# 08_-_PERIPHERALS_C.net
KiCad netlist of a schematic drawn in Altium Designer
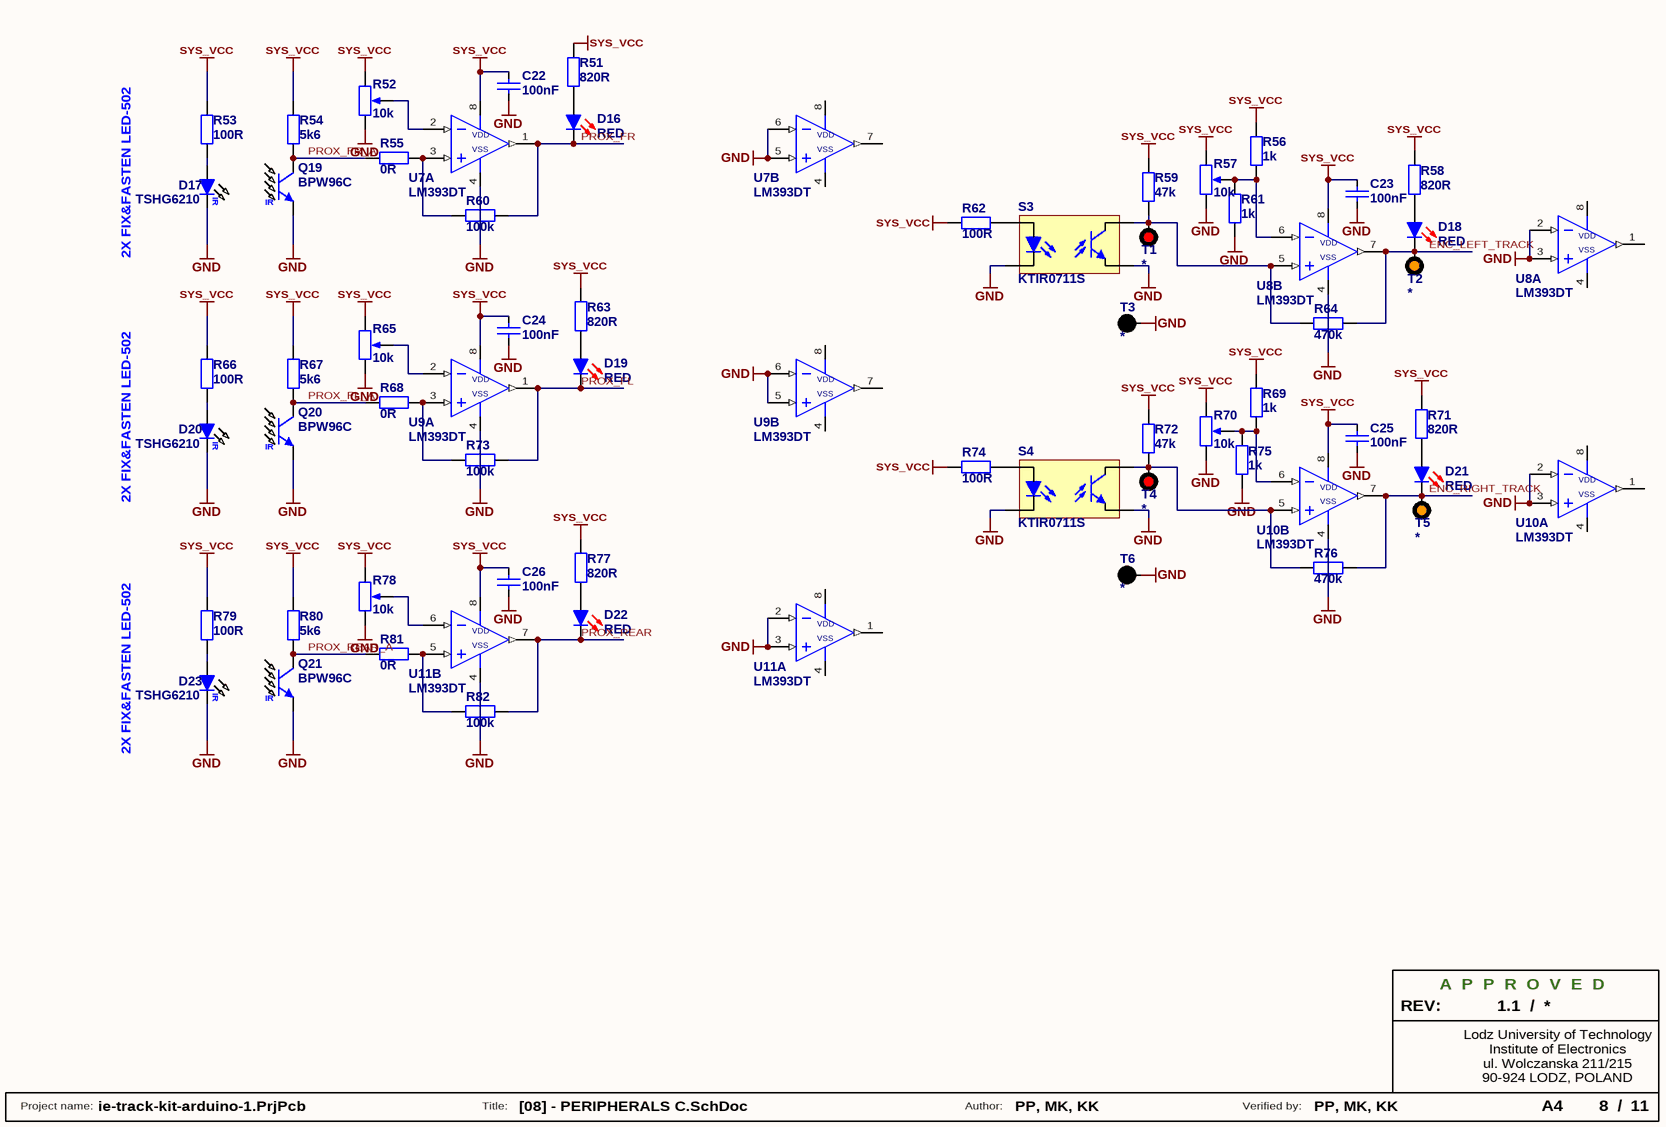
[diagram p0: [08] - PERIPHERALS C.SchDoc]

(export (version "E")
  (design (tool "Eeschema 10.0.6"))
  (components
    (comp (ref "C22")
      (value "100nF")
      (footprint "C0805")
      (description "Capacitor")
      (libsource (lib "capacitors") (part "Cap"))
    )
    (comp (ref "C23")
      (value "100nF")
      (footprint "C0805")
      (description "Capacitor")
      (libsource (lib "capacitors") (part "Cap"))
    )
    (comp (ref "C24")
      (value "100nF")
      (footprint "C0805")
      (description "Capacitor")
      (libsource (lib "capacitors") (part "Cap"))
    )
    (comp (ref "C25")
      (value "100nF")
      (footprint "C0805")
      (description "Capacitor")
      (libsource (lib "capacitors") (part "Cap"))
    )
    (comp (ref "C26")
      (value "100nF")
      (footprint "C0805")
      (description "Capacitor")
      (libsource (lib "capacitors") (part "Cap"))
    )
    (comp (ref "D16")
      (value "RED")
      (footprint "LED0805R")
      (description "RED LED")
      (libsource (lib "leds") (part "LED_RED"))
    )
    (comp (ref "D17")
      (value "TSHG6210")
      (footprint "LED-502")
      (description "IR transmitter; 5mm; 850nm; transparent; 230mW; 10°; THT; 1.5÷1.8V")
      (libsource (lib "leds") (part "TSHG6210"))
    )
    (comp (ref "D18")
      (value "RED")
      (footprint "LED0805R")
      (description "RED LED")
      (libsource (lib "leds") (part "LED_RED"))
    )
    (comp (ref "D19")
      (value "RED")
      (footprint "LED0805R")
      (description "RED LED")
      (libsource (lib "leds") (part "LED_RED"))
    )
    (comp (ref "D20")
      (value "TSHG6210")
      (footprint "LED-502")
      (description "IR transmitter; 5mm; 850nm; transparent; 230mW; 10°; THT; 1.5÷1.8V")
      (libsource (lib "leds") (part "TSHG6210"))
    )
    (comp (ref "D21")
      (value "RED")
      (footprint "LED0805R")
      (description "RED LED")
      (libsource (lib "leds") (part "LED_RED"))
    )
    (comp (ref "D22")
      (value "RED")
      (footprint "LED0805R")
      (description "RED LED")
      (libsource (lib "leds") (part "LED_RED"))
    )
    (comp (ref "D23")
      (value "TSHG6210")
      (footprint "LED-502")
      (description "IR transmitter; 5mm; 850nm; transparent; 230mW; 10°; THT; 1.5÷1.8V")
      (libsource (lib "leds") (part "TSHG6210"))
    )
    (comp (ref "Q19")
      (value "BPW96C")
      (footprint "LED-502")
      (description "Phototransistor; λp max:850nm; 70V; 20°; Lens: transparent; Ø:5mm")
      (libsource (lib "photoelements") (part "BPW96C"))
    )
    (comp (ref "Q20")
      (value "BPW96C")
      (footprint "LED-502")
      (description "Phototransistor; λp max:850nm; 70V; 20°; Lens: transparent; Ø:5mm")
      (libsource (lib "photoelements") (part "BPW96C"))
    )
    (comp (ref "Q21")
      (value "BPW96C")
      (footprint "LED-502")
      (description "Phototransistor; λp max:850nm; 70V; 20°; Lens: transparent; Ø:5mm")
      (libsource (lib "photoelements") (part "BPW96C"))
    )
    (comp (ref "R51")
      (value "820R")
      (footprint "R0805")
      (description "Resistor")
      (libsource (lib "") (part "Res_1"))
    )
    (comp (ref "R52")
      (value "10k")
      (footprint "3305SMD")
      (description "3305SMD-10K")
      (libsource (lib "resistors") (part "3305SMD-10K"))
    )
    (comp (ref "R53")
      (value "100R")
      (footprint "R0805")
      (description "Resistor")
      (libsource (lib "") (part "Res_1"))
    )
    (comp (ref "R54")
      (value "5k6")
      (footprint "R0805")
      (description "Resistor")
      (libsource (lib "") (part "Res_1"))
    )
    (comp (ref "R55")
      (value "0R")
      (footprint "R0805")
      (description "Resistor")
      (libsource (lib "resistors") (part "Res"))
    )
    (comp (ref "R56")
      (value "1k")
      (footprint "R0805")
      (description "Resistor")
      (libsource (lib "") (part "Res_1"))
    )
    (comp (ref "R57")
      (value "10k")
      (footprint "3305SMD")
      (description "3305SMD-10K")
      (libsource (lib "resistors") (part "3305SMD-10K"))
    )
    (comp (ref "R58")
      (value "820R")
      (footprint "R0805")
      (description "Resistor")
      (libsource (lib "") (part "Res_1"))
    )
    (comp (ref "R59")
      (value "47k")
      (footprint "R0805")
      (description "Resistor")
      (libsource (lib "") (part "Res_3"))
    )
    (comp (ref "R60")
      (value "100k")
      (footprint "R0805")
      (description "Resistor")
      (libsource (lib "resistors") (part "Res"))
    )
    (comp (ref "R61")
      (value "1k")
      (footprint "R0805")
      (description "Resistor")
      (libsource (lib "") (part "Res_1"))
    )
    (comp (ref "R62")
      (value "100R")
      (footprint "R0805")
      (description "Resistor")
      (libsource (lib "") (part "Res_2"))
    )
    (comp (ref "R63")
      (value "820R")
      (footprint "R0805")
      (description "Resistor")
      (libsource (lib "") (part "Res_1"))
    )
    (comp (ref "R64")
      (value "470k")
      (footprint "R0805")
      (description "Resistor")
      (libsource (lib "resistors") (part "Res"))
    )
    (comp (ref "R65")
      (value "10k")
      (footprint "3305SMD")
      (description "3305SMD-10K")
      (libsource (lib "resistors") (part "3305SMD-10K"))
    )
    (comp (ref "R66")
      (value "100R")
      (footprint "R0805")
      (description "Resistor")
      (libsource (lib "") (part "Res_1"))
    )
    (comp (ref "R67")
      (value "5k6")
      (footprint "R0805")
      (description "Resistor")
      (libsource (lib "") (part "Res_1"))
    )
    (comp (ref "R68")
      (value "0R")
      (footprint "R0805")
      (description "Resistor")
      (libsource (lib "resistors") (part "Res"))
    )
    (comp (ref "R69")
      (value "1k")
      (footprint "R0805")
      (description "Resistor")
      (libsource (lib "") (part "Res_1"))
    )
    (comp (ref "R70")
      (value "10k")
      (footprint "3305SMD")
      (description "3305SMD-10K")
      (libsource (lib "resistors") (part "3305SMD-10K"))
    )
    (comp (ref "R71")
      (value "820R")
      (footprint "R0805")
      (description "Resistor")
      (libsource (lib "") (part "Res_1"))
    )
    (comp (ref "R72")
      (value "47k")
      (footprint "R0805")
      (description "Resistor")
      (libsource (lib "") (part "Res_3"))
    )
    (comp (ref "R73")
      (value "100k")
      (footprint "R0805")
      (description "Resistor")
      (libsource (lib "resistors") (part "Res"))
    )
    (comp (ref "R74")
      (value "100R")
      (footprint "R0805")
      (description "Resistor")
      (libsource (lib "") (part "Res_2"))
    )
    (comp (ref "R75")
      (value "1k")
      (footprint "R0805")
      (description "Resistor")
      (libsource (lib "") (part "Res_1"))
    )
    (comp (ref "R76")
      (value "470k")
      (footprint "R0805")
      (description "Resistor")
      (libsource (lib "resistors") (part "Res"))
    )
    (comp (ref "R77")
      (value "820R")
      (footprint "R0805")
      (description "Resistor")
      (libsource (lib "") (part "Res_1"))
    )
    (comp (ref "R78")
      (value "10k")
      (footprint "3305SMD")
      (description "3305SMD-10K")
      (libsource (lib "resistors") (part "3305SMD-10K"))
    )
    (comp (ref "R79")
      (value "100R")
      (footprint "R0805")
      (description "Resistor")
      (libsource (lib "") (part "Res_1"))
    )
    (comp (ref "R80")
      (value "5k6")
      (footprint "R0805")
      (description "Resistor")
      (libsource (lib "") (part "Res_1"))
    )
    (comp (ref "R81")
      (value "0R")
      (footprint "R0805")
      (description "Resistor")
      (libsource (lib "resistors") (part "Res"))
    )
    (comp (ref "R82")
      (value "100k")
      (footprint "R0805")
      (description "Resistor")
      (libsource (lib "resistors") (part "Res"))
    )
    (comp (ref "S3")
      (value "KTIR0711S")
      (footprint "KTIR0711S_wide_pads")
      (description "SUBMINIATURE, HIGH SENSITIVITY PHOTOINTERRUPTER")
      (libsource (lib "photoelectric_sensors") (part "KTIR0711S"))
    )
    (comp (ref "S4")
      (value "KTIR0711S")
      (footprint "KTIR0711S_wide_pads")
      (description "SUBMINIATURE, HIGH SENSITIVITY PHOTOINTERRUPTER")
      (libsource (lib "photoelectric_sensors") (part "KTIR0711S"))
    )
    (comp (ref "T1")
      (value "*")
      (footprint "Keystone_5000_RED")
      (description "Keystone 5000 Test Point (RED)")
      (libsource (lib "test_points") (part "Keystone 5000 Test Point"))
    )
    (comp (ref "T2")
      (value "*")
      (footprint "Keystone_5003_ORANGE")
      (description "Keystone 5003 Test Point (ORANGE)")
      (libsource (lib "test_points") (part "Keystone 5003 Test Point"))
    )
    (comp (ref "T3")
      (value "*")
      (footprint "Keystone_5001_BLACK")
      (description "Keystone 5001 Test Point (BLACK)")
      (libsource (lib "test_points") (part "Keystone 5001 Test Point"))
    )
    (comp (ref "T4")
      (value "*")
      (footprint "Keystone_5000_RED")
      (description "Keystone 5000 Test Point (RED)")
      (libsource (lib "test_points") (part "Keystone 5000 Test Point"))
    )
    (comp (ref "T5")
      (value "*")
      (footprint "Keystone_5003_ORANGE")
      (description "Keystone 5003 Test Point (ORANGE)")
      (libsource (lib "test_points") (part "Keystone 5003 Test Point"))
    )
    (comp (ref "T6")
      (value "*")
      (footprint "Keystone_5001_BLACK")
      (description "Keystone 5001 Test Point (BLACK)")
      (libsource (lib "test_points") (part "Keystone 5001 Test Point"))
    )
    (comp (ref "U7")
      (value "LM393DT")
      (footprint "SO8")
      (description "Low power dual voltage comparators")
      (libsource (lib "comparators") (part "LM393DT"))
    )
    (comp (ref "U8")
      (value "LM393DT")
      (footprint "SO8")
      (description "Low power dual voltage comparators")
      (libsource (lib "comparators") (part "LM393DT"))
    )
    (comp (ref "U9")
      (value "LM393DT")
      (footprint "SO8")
      (description "Low power dual voltage comparators")
      (libsource (lib "comparators") (part "LM393DT"))
    )
    (comp (ref "U10")
      (value "LM393DT")
      (footprint "SO8")
      (description "Low power dual voltage comparators")
      (libsource (lib "comparators") (part "LM393DT"))
    )
    (comp (ref "U11")
      (value "LM393DT")
      (footprint "SO8")
      (description "Low power dual voltage comparators")
      (libsource (lib "comparators") (part "LM393DT"))
    )
  )
  (nets
    (net (code "1") (name "/ENC_LEFT_TRACK") (class "Default")
      (node (ref "D18") (pin "2") (pinfunction "K_2") (pintype "passive"))
      (node (ref "R64") (pin "2") (pinfunction "2_2") (pintype "passive"))
      (node (ref "T2") (pin "0") (pinfunction "0_0") (pintype "passive"))
      (node (ref "U8") (pin "7") (pinfunction "OUT_7") (pintype "output"))
    )
    (net (code "2") (name "/ENC_RIGHT_TRACK") (class "Default")
      (node (ref "D21") (pin "2") (pinfunction "K_2") (pintype "passive"))
      (node (ref "R76") (pin "2") (pinfunction "2_2") (pintype "passive"))
      (node (ref "T5") (pin "0") (pinfunction "0_0") (pintype "passive"))
      (node (ref "U10") (pin "7") (pinfunction "OUT_7") (pintype "output"))
    )
    (net (code "3") (name "/PROX_FL") (class "Default")
      (node (ref "D19") (pin "2") (pinfunction "K_2") (pintype "passive"))
      (node (ref "R73") (pin "2") (pinfunction "2_2") (pintype "passive"))
      (node (ref "U9") (pin "1") (pinfunction "OUT_1") (pintype "output"))
    )
    (net (code "4") (name "/PROX_FL_A") (class "Default")
      (node (ref "Q20") (pin "2") (pinfunction "C_2") (pintype "passive"))
      (node (ref "R67") (pin "2") (pinfunction "2_2") (pintype "passive"))
      (node (ref "R68") (pin "1") (pinfunction "1_1") (pintype "passive"))
    )
    (net (code "5") (name "/PROX_FR") (class "Default")
      (node (ref "D16") (pin "2") (pinfunction "K_2") (pintype "passive"))
      (node (ref "R60") (pin "2") (pinfunction "2_2") (pintype "passive"))
      (node (ref "U7") (pin "1") (pinfunction "OUT_1") (pintype "output"))
    )
    (net (code "6") (name "/PROX_FR_A") (class "Default")
      (node (ref "Q19") (pin "2") (pinfunction "C_2") (pintype "passive"))
      (node (ref "R54") (pin "2") (pinfunction "2_2") (pintype "passive"))
      (node (ref "R55") (pin "1") (pinfunction "1_1") (pintype "passive"))
    )
    (net (code "7") (name "/PROX_REAR") (class "Default")
      (node (ref "D22") (pin "2") (pinfunction "K_2") (pintype "passive"))
      (node (ref "R82") (pin "2") (pinfunction "2_2") (pintype "passive"))
      (node (ref "U11") (pin "7") (pinfunction "OUT_7") (pintype "output"))
    )
    (net (code "8") (name "/PROX_REAR_A") (class "Default")
      (node (ref "Q21") (pin "2") (pinfunction "C_2") (pintype "passive"))
      (node (ref "R80") (pin "2") (pinfunction "2_2") (pintype "passive"))
      (node (ref "R81") (pin "1") (pinfunction "1_1") (pintype "passive"))
    )
    (net (code "9") (name "GND") (class "Default")
      (node (ref "C22") (pin "2") (pinfunction "2_2") (pintype "passive"))
      (node (ref "C23") (pin "2") (pinfunction "2_2") (pintype "passive"))
      (node (ref "C24") (pin "2") (pinfunction "2_2") (pintype "passive"))
      (node (ref "C25") (pin "2") (pinfunction "2_2") (pintype "passive"))
      (node (ref "C26") (pin "2") (pinfunction "2_2") (pintype "passive"))
      (node (ref "D17") (pin "2") (pinfunction "K_2") (pintype "passive"))
      (node (ref "D20") (pin "2") (pinfunction "K_2") (pintype "passive"))
      (node (ref "D23") (pin "2") (pinfunction "K_2") (pintype "passive"))
      (node (ref "Q19") (pin "1") (pinfunction "E_1") (pintype "passive"))
      (node (ref "Q20") (pin "1") (pinfunction "E_1") (pintype "passive"))
      (node (ref "Q21") (pin "1") (pinfunction "E_1") (pintype "passive"))
      (node (ref "R52") (pin "2") (pinfunction "BOT_2") (pintype "passive"))
      (node (ref "R57") (pin "2") (pinfunction "BOT_2") (pintype "passive"))
      (node (ref "R61") (pin "2") (pinfunction "2_2") (pintype "passive"))
      (node (ref "R65") (pin "2") (pinfunction "BOT_2") (pintype "passive"))
      (node (ref "R70") (pin "2") (pinfunction "BOT_2") (pintype "passive"))
      (node (ref "R75") (pin "2") (pinfunction "2_2") (pintype "passive"))
      (node (ref "R78") (pin "2") (pinfunction "BOT_2") (pintype "passive"))
      (node (ref "S3") (pin "2") (pinfunction "E_2") (pintype "passive"))
      (node (ref "S3") (pin "4") (pinfunction "K_4") (pintype "passive"))
      (node (ref "S4") (pin "2") (pinfunction "E_2") (pintype "passive"))
      (node (ref "S4") (pin "4") (pinfunction "K_4") (pintype "passive"))
      (node (ref "T3") (pin "0") (pinfunction "0_0") (pintype "passive"))
      (node (ref "T6") (pin "0") (pinfunction "0_0") (pintype "passive"))
      (node (ref "U10") (pin "2") (pinfunction "IN-_2") (pintype "input"))
      (node (ref "U10") (pin "3") (pinfunction "IN+_3") (pintype "input"))
      (node (ref "U10") (pin "4") (pinfunction "GND_4") (pintype "power_in"))
      (node (ref "U11") (pin "2") (pinfunction "IN-_2") (pintype "input"))
      (node (ref "U11") (pin "3") (pinfunction "IN+_3") (pintype "input"))
      (node (ref "U11") (pin "4") (pinfunction "GND_4") (pintype "power_in"))
      (node (ref "U7") (pin "4") (pinfunction "GND_4") (pintype "power_in"))
      (node (ref "U7") (pin "5") (pinfunction "IN+_5") (pintype "input"))
      (node (ref "U7") (pin "6") (pinfunction "IN-_6") (pintype "input"))
      (node (ref "U8") (pin "2") (pinfunction "IN-_2") (pintype "input"))
      (node (ref "U8") (pin "3") (pinfunction "IN+_3") (pintype "input"))
      (node (ref "U8") (pin "4") (pinfunction "GND_4") (pintype "power_in"))
      (node (ref "U9") (pin "4") (pinfunction "GND_4") (pintype "power_in"))
      (node (ref "U9") (pin "5") (pinfunction "IN+_5") (pintype "input"))
      (node (ref "U9") (pin "6") (pinfunction "IN-_6") (pintype "input"))
    )
    (net (code "10") (name "Net-(D16-A)") (class "Default")
      (node (ref "D16") (pin "1") (pinfunction "A_1") (pintype "passive"))
      (node (ref "R51") (pin "2") (pinfunction "2_2") (pintype "passive"))
    )
    (net (code "11") (name "Net-(D17-A)") (class "Default")
      (node (ref "D17") (pin "1") (pinfunction "A_1") (pintype "passive"))
      (node (ref "R53") (pin "2") (pinfunction "2_2") (pintype "passive"))
    )
    (net (code "12") (name "Net-(D18-A)") (class "Default")
      (node (ref "D18") (pin "1") (pinfunction "A_1") (pintype "passive"))
      (node (ref "R58") (pin "2") (pinfunction "2_2") (pintype "passive"))
    )
    (net (code "13") (name "Net-(D19-A)") (class "Default")
      (node (ref "D19") (pin "1") (pinfunction "A_1") (pintype "passive"))
      (node (ref "R63") (pin "2") (pinfunction "2_2") (pintype "passive"))
    )
    (net (code "14") (name "Net-(D20-A)") (class "Default")
      (node (ref "D20") (pin "1") (pinfunction "A_1") (pintype "passive"))
      (node (ref "R66") (pin "2") (pinfunction "2_2") (pintype "passive"))
    )
    (net (code "15") (name "Net-(D21-A)") (class "Default")
      (node (ref "D21") (pin "1") (pinfunction "A_1") (pintype "passive"))
      (node (ref "R71") (pin "2") (pinfunction "2_2") (pintype "passive"))
    )
    (net (code "16") (name "Net-(D22-A)") (class "Default")
      (node (ref "D22") (pin "1") (pinfunction "A_1") (pintype "passive"))
      (node (ref "R77") (pin "2") (pinfunction "2_2") (pintype "passive"))
    )
    (net (code "17") (name "Net-(D23-A)") (class "Default")
      (node (ref "D23") (pin "1") (pinfunction "A_1") (pintype "passive"))
      (node (ref "R79") (pin "2") (pinfunction "2_2") (pintype "passive"))
    )
    (net (code "18") (name "Net-(R52-TAP)") (class "Default")
      (node (ref "R52") (pin "3") (pinfunction "TAP_3") (pintype "passive"))
      (node (ref "U7") (pin "2") (pinfunction "IN-_2") (pintype "input"))
    )
    (net (code "19") (name "Net-(R57-TAP)") (class "Default")
      (node (ref "R56") (pin "2") (pinfunction "2_2") (pintype "passive"))
      (node (ref "R57") (pin "3") (pinfunction "TAP_3") (pintype "passive"))
      (node (ref "R61") (pin "1") (pinfunction "1_1") (pintype "passive"))
      (node (ref "U8") (pin "6") (pinfunction "IN-_6") (pintype "input"))
    )
    (net (code "20") (name "Net-(R65-TAP)") (class "Default")
      (node (ref "R65") (pin "3") (pinfunction "TAP_3") (pintype "passive"))
      (node (ref "U9") (pin "2") (pinfunction "IN-_2") (pintype "input"))
    )
    (net (code "21") (name "Net-(R70-TAP)") (class "Default")
      (node (ref "R69") (pin "2") (pinfunction "2_2") (pintype "passive"))
      (node (ref "R70") (pin "3") (pinfunction "TAP_3") (pintype "passive"))
      (node (ref "R75") (pin "1") (pinfunction "1_1") (pintype "passive"))
      (node (ref "U10") (pin "6") (pinfunction "IN-_6") (pintype "input"))
    )
    (net (code "22") (name "Net-(R78-TAP)") (class "Default")
      (node (ref "R78") (pin "3") (pinfunction "TAP_3") (pintype "passive"))
      (node (ref "U11") (pin "6") (pinfunction "IN-_6") (pintype "input"))
    )
    (net (code "23") (name "Net-(S3-A)") (class "Default")
      (node (ref "R62") (pin "1") (pinfunction "1_1") (pintype "passive"))
      (node (ref "S3") (pin "1") (pinfunction "A_1") (pintype "passive"))
    )
    (net (code "24") (name "Net-(S3-C)") (class "Default")
      (node (ref "R59") (pin "1") (pinfunction "1_1") (pintype "passive"))
      (node (ref "R64") (pin "1") (pinfunction "1_1") (pintype "passive"))
      (node (ref "S3") (pin "3") (pinfunction "C_3") (pintype "passive"))
      (node (ref "T1") (pin "0") (pinfunction "0_0") (pintype "passive"))
      (node (ref "U8") (pin "5") (pinfunction "IN+_5") (pintype "input"))
    )
    (net (code "25") (name "Net-(S4-A)") (class "Default")
      (node (ref "R74") (pin "1") (pinfunction "1_1") (pintype "passive"))
      (node (ref "S4") (pin "1") (pinfunction "A_1") (pintype "passive"))
    )
    (net (code "26") (name "Net-(S4-C)") (class "Default")
      (node (ref "R72") (pin "1") (pinfunction "1_1") (pintype "passive"))
      (node (ref "R76") (pin "1") (pinfunction "1_1") (pintype "passive"))
      (node (ref "S4") (pin "3") (pinfunction "C_3") (pintype "passive"))
      (node (ref "T4") (pin "0") (pinfunction "0_0") (pintype "passive"))
      (node (ref "U10") (pin "5") (pinfunction "IN+_5") (pintype "input"))
    )
    (net (code "27") (name "Net-(U7A-IN+)") (class "Default")
      (node (ref "R55") (pin "2") (pinfunction "2_2") (pintype "passive"))
      (node (ref "R60") (pin "1") (pinfunction "1_1") (pintype "passive"))
      (node (ref "U7") (pin "3") (pinfunction "IN+_3") (pintype "input"))
    )
    (net (code "28") (name "Net-(U9A-IN+)") (class "Default")
      (node (ref "R68") (pin "2") (pinfunction "2_2") (pintype "passive"))
      (node (ref "R73") (pin "1") (pinfunction "1_1") (pintype "passive"))
      (node (ref "U9") (pin "3") (pinfunction "IN+_3") (pintype "input"))
    )
    (net (code "29") (name "Net-(U11B-IN+)") (class "Default")
      (node (ref "R81") (pin "2") (pinfunction "2_2") (pintype "passive"))
      (node (ref "R82") (pin "1") (pinfunction "1_1") (pintype "passive"))
      (node (ref "U11") (pin "5") (pinfunction "IN+_5") (pintype "input"))
    )
    (net (code "30") (name "SYS_VCC") (class "Default")
      (node (ref "C22") (pin "1") (pinfunction "1_1") (pintype "passive"))
      (node (ref "C23") (pin "1") (pinfunction "1_1") (pintype "passive"))
      (node (ref "C24") (pin "1") (pinfunction "1_1") (pintype "passive"))
      (node (ref "C25") (pin "1") (pinfunction "1_1") (pintype "passive"))
      (node (ref "C26") (pin "1") (pinfunction "1_1") (pintype "passive"))
      (node (ref "R51") (pin "1") (pinfunction "1_1") (pintype "passive"))
      (node (ref "R52") (pin "1") (pinfunction "TOP_1") (pintype "passive"))
      (node (ref "R53") (pin "1") (pinfunction "1_1") (pintype "passive"))
      (node (ref "R54") (pin "1") (pinfunction "1_1") (pintype "passive"))
      (node (ref "R56") (pin "1") (pinfunction "1_1") (pintype "passive"))
      (node (ref "R57") (pin "1") (pinfunction "TOP_1") (pintype "passive"))
      (node (ref "R58") (pin "1") (pinfunction "1_1") (pintype "passive"))
      (node (ref "R59") (pin "2") (pinfunction "2_2") (pintype "passive"))
      (node (ref "R62") (pin "2") (pinfunction "2_2") (pintype "passive"))
      (node (ref "R63") (pin "1") (pinfunction "1_1") (pintype "passive"))
      (node (ref "R65") (pin "1") (pinfunction "TOP_1") (pintype "passive"))
      (node (ref "R66") (pin "1") (pinfunction "1_1") (pintype "passive"))
      (node (ref "R67") (pin "1") (pinfunction "1_1") (pintype "passive"))
      (node (ref "R69") (pin "1") (pinfunction "1_1") (pintype "passive"))
      (node (ref "R70") (pin "1") (pinfunction "TOP_1") (pintype "passive"))
      (node (ref "R71") (pin "1") (pinfunction "1_1") (pintype "passive"))
      (node (ref "R72") (pin "2") (pinfunction "2_2") (pintype "passive"))
      (node (ref "R74") (pin "2") (pinfunction "2_2") (pintype "passive"))
      (node (ref "R77") (pin "1") (pinfunction "1_1") (pintype "passive"))
      (node (ref "R78") (pin "1") (pinfunction "TOP_1") (pintype "passive"))
      (node (ref "R79") (pin "1") (pinfunction "1_1") (pintype "passive"))
      (node (ref "R80") (pin "1") (pinfunction "1_1") (pintype "passive"))
      (node (ref "U10") (pin "8") (pinfunction "V+_8") (pintype "power_in"))
      (node (ref "U11") (pin "8") (pinfunction "V+_8") (pintype "power_in"))
      (node (ref "U7") (pin "8") (pinfunction "V+_8") (pintype "power_in"))
      (node (ref "U8") (pin "8") (pinfunction "V+_8") (pintype "power_in"))
      (node (ref "U9") (pin "8") (pinfunction "V+_8") (pintype "power_in"))
    )
    (net (code "31") (name "unconnected-(U7B-GND-Pad4)") (class "Default")
      (node (ref "U7") (pin "4") (pinfunction "GND_4") (pintype "power_in"))
    )
    (net (code "32") (name "unconnected-(U7B-OUT-Pad7)") (class "Default")
      (node (ref "U7") (pin "7") (pinfunction "OUT_7") (pintype "output"))
    )
    (net (code "33") (name "unconnected-(U7B-V+-Pad8)") (class "Default")
      (node (ref "U7") (pin "8") (pinfunction "V+_8") (pintype "power_in"))
    )
    (net (code "34") (name "unconnected-(U8A-GND-Pad4)") (class "Default")
      (node (ref "U8") (pin "4") (pinfunction "GND_4") (pintype "power_in"))
    )
    (net (code "35") (name "unconnected-(U8A-OUT-Pad1)") (class "Default")
      (node (ref "U8") (pin "1") (pinfunction "OUT_1") (pintype "output"))
    )
    (net (code "36") (name "unconnected-(U8A-V+-Pad8)") (class "Default")
      (node (ref "U8") (pin "8") (pinfunction "V+_8") (pintype "power_in"))
    )
    (net (code "37") (name "unconnected-(U9B-GND-Pad4)") (class "Default")
      (node (ref "U9") (pin "4") (pinfunction "GND_4") (pintype "power_in"))
    )
    (net (code "38") (name "unconnected-(U9B-OUT-Pad7)") (class "Default")
      (node (ref "U9") (pin "7") (pinfunction "OUT_7") (pintype "output"))
    )
    (net (code "39") (name "unconnected-(U9B-V+-Pad8)") (class "Default")
      (node (ref "U9") (pin "8") (pinfunction "V+_8") (pintype "power_in"))
    )
    (net (code "40") (name "unconnected-(U10A-GND-Pad4)") (class "Default")
      (node (ref "U10") (pin "4") (pinfunction "GND_4") (pintype "power_in"))
    )
    (net (code "41") (name "unconnected-(U10A-OUT-Pad1)") (class "Default")
      (node (ref "U10") (pin "1") (pinfunction "OUT_1") (pintype "output"))
    )
    (net (code "42") (name "unconnected-(U10A-V+-Pad8)") (class "Default")
      (node (ref "U10") (pin "8") (pinfunction "V+_8") (pintype "power_in"))
    )
    (net (code "43") (name "unconnected-(U11A-GND-Pad4)") (class "Default")
      (node (ref "U11") (pin "4") (pinfunction "GND_4") (pintype "power_in"))
    )
    (net (code "44") (name "unconnected-(U11A-OUT-Pad1)") (class "Default")
      (node (ref "U11") (pin "1") (pinfunction "OUT_1") (pintype "output"))
    )
    (net (code "45") (name "unconnected-(U11A-V+-Pad8)") (class "Default")
      (node (ref "U11") (pin "8") (pinfunction "V+_8") (pintype "power_in"))
    )
  )
)
